# acceleration_particul_ariel.net
KiCad netlist of a schematic drawn in EasyEDA
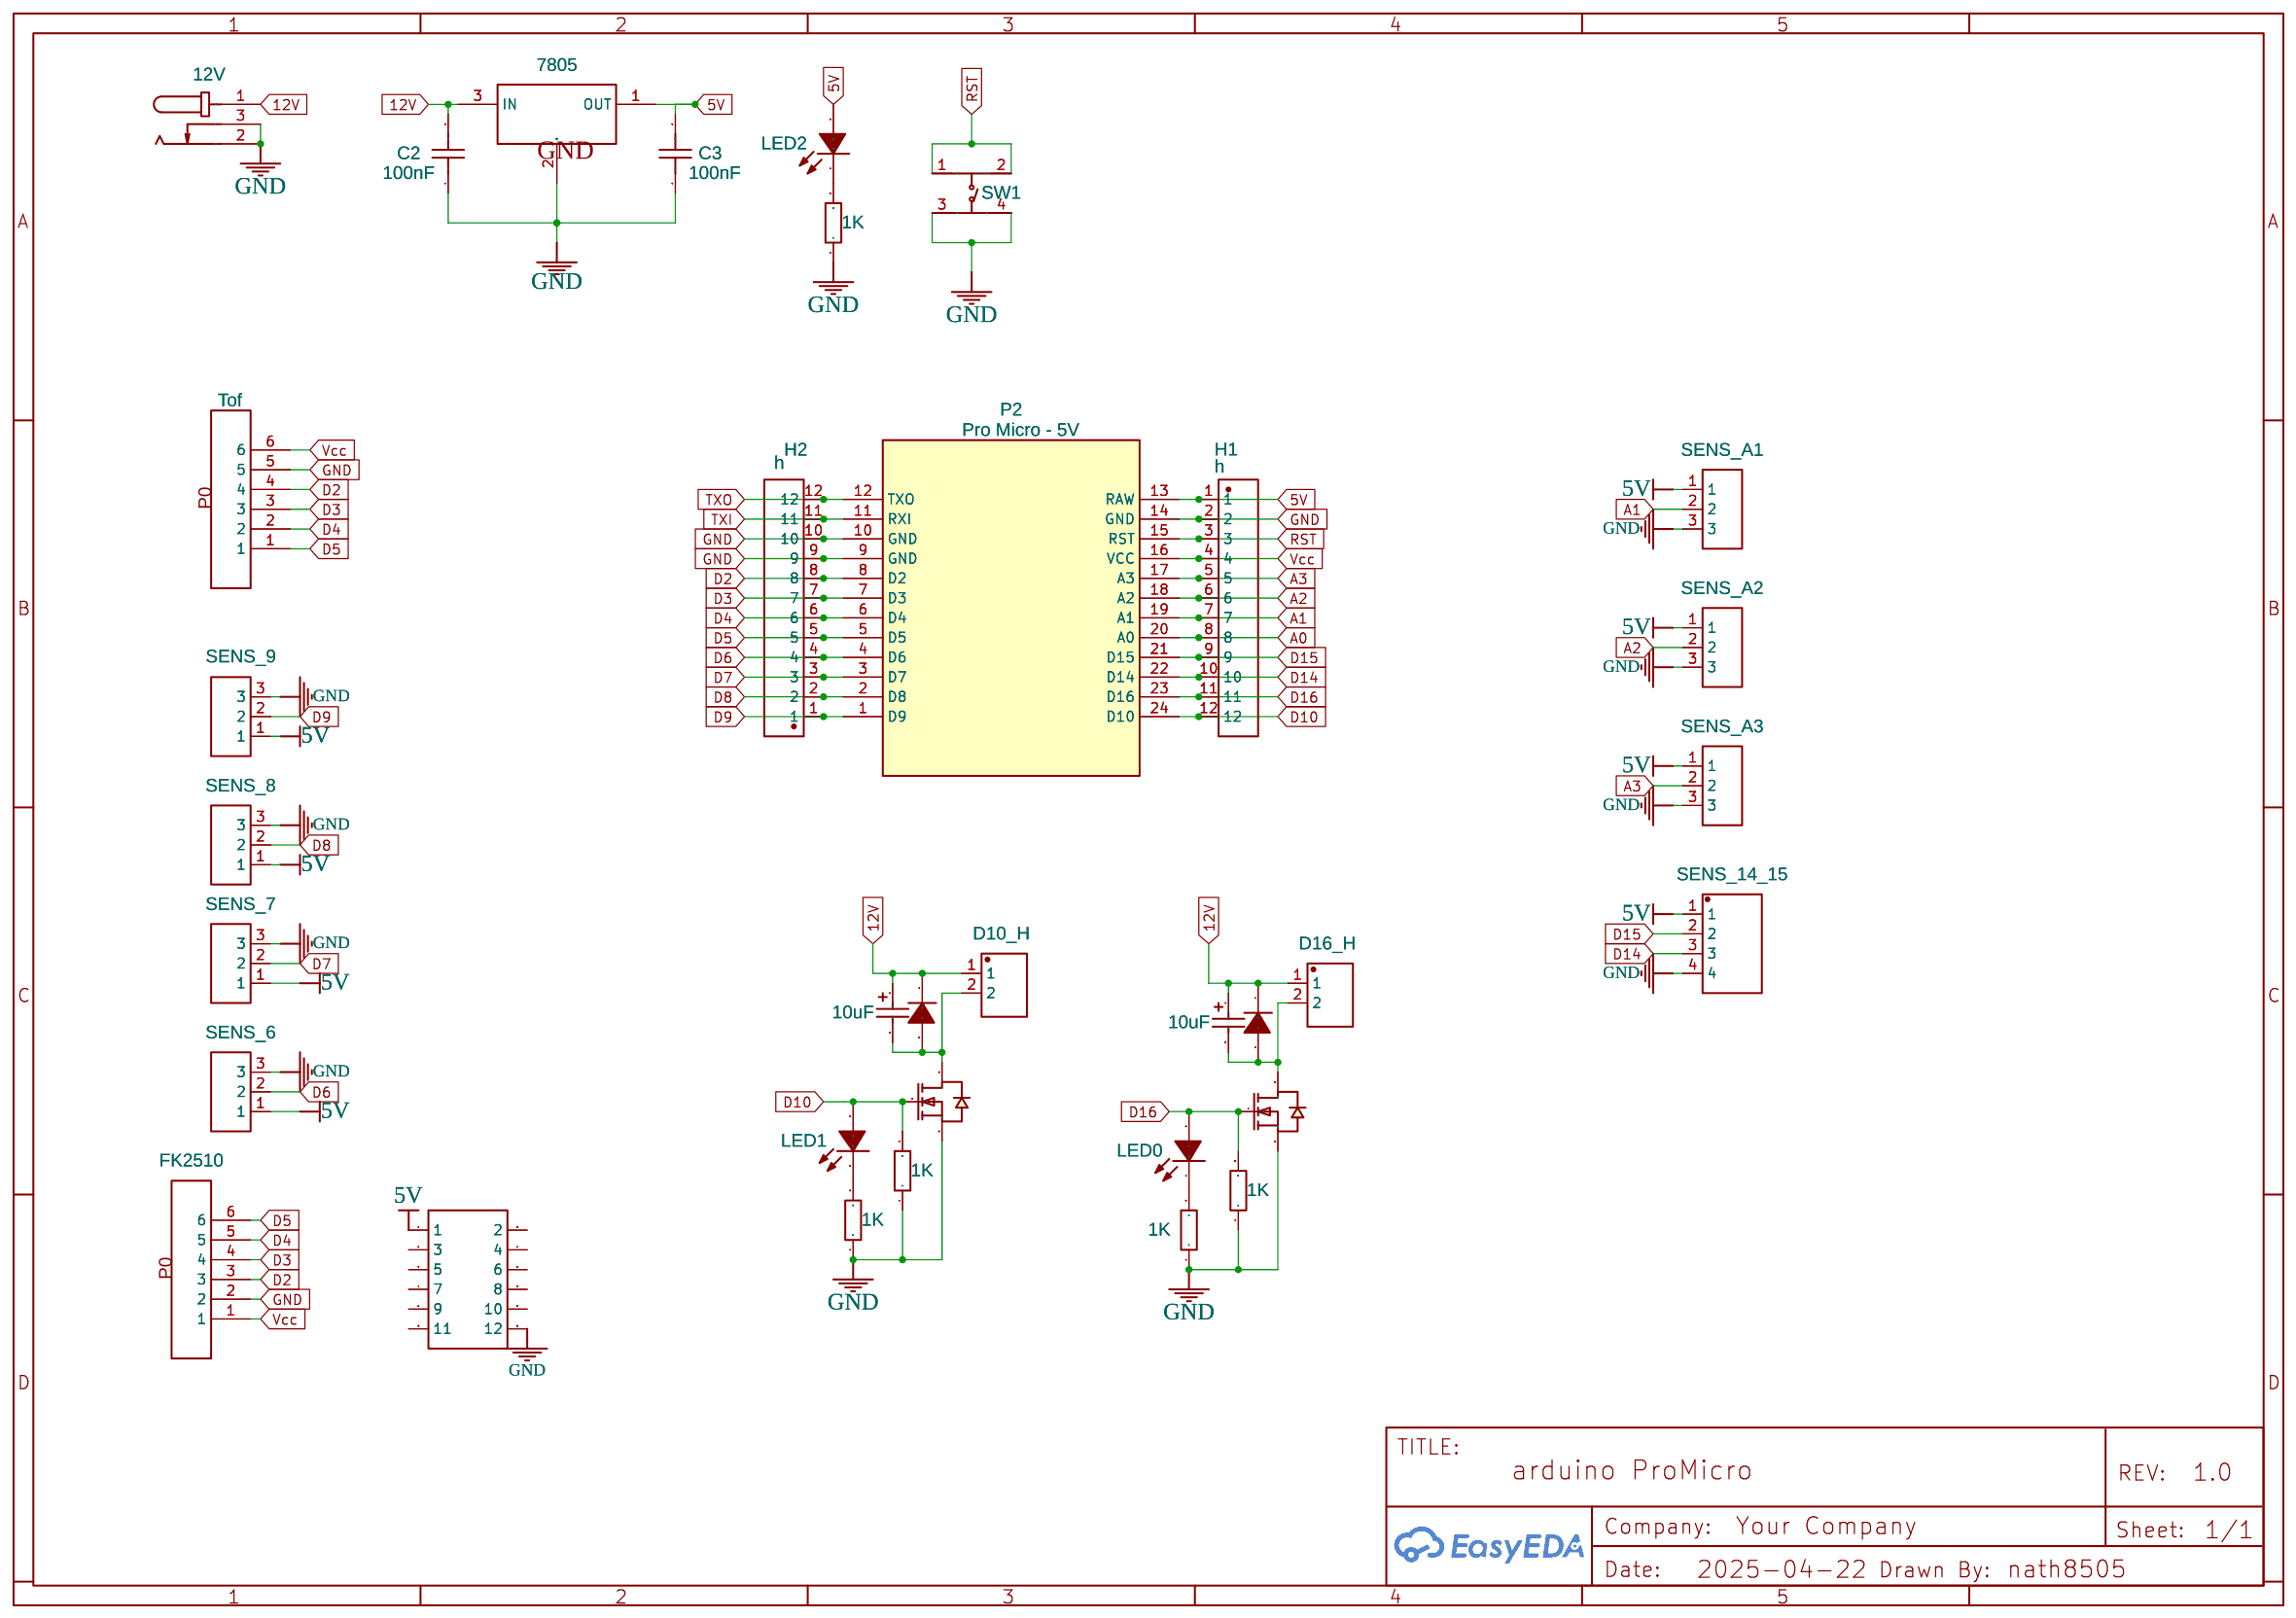
[diagram p0: schematic sheet]

(export (version "E")
  (design (tool "Eeschema 10.0.6"))
  (components
    (comp (ref "12V")
      (value "12V")
      (fields (field (name "Manufacturer Part") "DC005-2.0MM") (field (name "Manufacturer") "SOFNG"))
      (libsource (lib "") (part "DC005-2.0MM"))
    )
    (comp (ref "7805")
      (value "SE78L05")
      (fields (field (name "Manufacturer") "SEAWARD(思旺)"))
      (libsource (lib "") (part "SE78L05"))
    )
    (comp (ref "C0") (value "10uF") (libsource (lib "") (part "TAJA106K016RNJ")))
    (comp (ref "C1") (value "10uF") (libsource (lib "") (part "TAJA106K016RNJ")))
    (comp (ref "C2") (value "100nF") (libsource (lib "") (part "CC0603KRX7R9BB104")))
    (comp (ref "C3") (value "100nF") (libsource (lib "") (part "CC0603KRX7R9BB104")))
    (comp (ref "D0")
      (value "1N4007")
      (fields (field (name "Manufacturer Part") "1N4007F") (field (name "Manufacturer") "SK"))
      (libsource (lib "") (part "1N4007F"))
    )
    (comp (ref "D1")
      (value "1N4007")
      (fields (field (name "Manufacturer Part") "1N4007F") (field (name "Manufacturer") "SK"))
      (libsource (lib "") (part "1N4007F"))
    )
    (comp (ref "D10_H")
      (value "KF2510-2A")
      (fields (field (name "Manufacturer") "BOOMELE"))
      (libsource (lib "") (part "KF2510-2A"))
    )
    (comp (ref "D16_H")
      (value "KF2510-2A")
      (fields (field (name "Manufacturer") "BOOMELE"))
      (libsource (lib "") (part "KF2510-2A_1"))
    )
    (comp (ref "H1")
      (value "h")
      (fields (field (name "Manufacturer Part") "DS1021-1x12SF11-B") (field (name "Manufacturer") "CONNFLY"))
      (libsource (lib "") (part "DS1021-1X12SF11-B"))
    )
    (comp (ref "H2")
      (value "h")
      (fields (field (name "Manufacturer Part") "DS1021-1x12SF11-B") (field (name "Manufacturer") "CONNFLY"))
      (libsource (lib "") (part "DS1021-1X12SF11-B_1"))
    )
    (comp (ref "H4")
      (value "Header-Female-2.54_2x6")
      (fields (field (name "Manufacturer Part") "2.54-2*6P母") (field (name "Manufacturer") "BOOMELE(博穆精密)"))
      (libsource (lib "") (part "Header-Female-2.54_2x6"))
    )
    (comp (ref "I2C_TOF1") (value "Tof") (libsource (lib "") (part "PinHeader6")))
    (comp (ref "I2C_TOF2") (value "FK2510") (libsource (lib "") (part "PinHeader6")))
    (comp (ref "LED0")
      (value "KT-0603R")
      (fields (field (name "Manufacturer") "KENTO"))
      (libsource (lib "") (part "KT-0603R"))
    )
    (comp (ref "LED1")
      (value "KT-0603R")
      (fields (field (name "Manufacturer") "KENTO"))
      (libsource (lib "") (part "KT-0603R"))
    )
    (comp (ref "LED2")
      (value "KT-0603R")
      (fields (field (name "Manufacturer") "KENTO"))
      (libsource (lib "") (part "KT-0603R"))
    )
    (comp (ref "P2") (value "Pro Micro - 5V") (libsource (lib "") (part "Pro Micro - 5V")))
    (comp (ref "R0")
      (value "1K")
      (fields (field (name "Manufacturer Part") "0603WAF1001T5E") (field (name "Manufacturer") "UniOhm"))
      (libsource (lib "") (part "0603WAF1001T5E"))
    )
    (comp (ref "R1")
      (value "1K")
      (fields (field (name "Manufacturer Part") "0603WAF1001T5E") (field (name "Manufacturer") "UniOhm"))
      (libsource (lib "") (part "0603WAF1001T5E"))
    )
    (comp (ref "R2")
      (value "1K")
      (fields (field (name "Manufacturer Part") "0603WAF1001T5E") (field (name "Manufacturer") "UniOhm"))
      (libsource (lib "") (part "0603WAF1001T5E"))
    )
    (comp (ref "R3")
      (value "1K")
      (fields (field (name "Manufacturer Part") "0603WAF1001T5E") (field (name "Manufacturer") "UniOhm"))
      (libsource (lib "") (part "0603WAF1001T5E"))
    )
    (comp (ref "R4")
      (value "1K")
      (fields (field (name "Manufacturer Part") "0603WAF1001T5E") (field (name "Manufacturer") "UniOhm"))
      (libsource (lib "") (part "0603WAF1001T5E"))
    )
    (comp (ref "SENS_6") (value "FK2510") (libsource (lib "") (part "kf2510_3A")))
    (comp (ref "SENS_7") (value "FK2510") (libsource (lib "") (part "kf2510_3A")))
    (comp (ref "SENS_8") (value "FK2510") (libsource (lib "") (part "kf2510_3A")))
    (comp (ref "SENS_9") (value "FK2510") (libsource (lib "") (part "kf2510_3A")))
    (comp (ref "SENS_14_15")
      (value "SENS_14_15")
      (fields
        (field (name "Manufacturer Part") "210S-1*4P L=11.6MMGold-plated black")
        (field (name "Manufacturer") "Ckmtw")
      )
      (libsource (lib "") (part "Conector KF2510_3A.ventilador.4pin"))
    )
    (comp (ref "SENS_A1") (value "FK2510") (libsource (lib "") (part "kf2510_3A_1")))
    (comp (ref "SENS_A2") (value "FK2510") (libsource (lib "") (part "kf2510_3A_1")))
    (comp (ref "SENS_A3") (value "FK2510") (libsource (lib "") (part "kf2510_3A_1")))
    (comp (ref "SW1")
      (value "TC-6610-7-160G")
      (fields (field (name "Manufacturer") "HCTL(华灿天禄)"))
      (libsource (lib "") (part "TC-6610-7-160G"))
    )
    (comp (ref "T1")
      (value "Q")
      (fields (field (name "Manufacturer Part") "AO3400") (field (name "Manufacturer") "ElecSuper(静芯微）"))
      (libsource (lib "") (part "JSM2302"))
    )
    (comp (ref "T2")
      (value "Q")
      (fields (field (name "Manufacturer Part") "AO3400") (field (name "Manufacturer") "ElecSuper(静芯微）"))
      (libsource (lib "") (part "JSM2302"))
    )
  )
  (nets
    (net (code "1") (name "5V") (class "Default")
      (node (ref "7805") (pin "1") (pinfunction "OUT_1") (pintype "passive"))
      (node (ref "C3") (pin "2") (pinfunction "2_2") (pintype "unspecified"))
      (node (ref "H1") (pin "1") (pinfunction "1_1") (pintype "unspecified"))
      (node (ref "H4") (pin "1") (pinfunction "1_1") (pintype "input"))
      (node (ref "LED2") (pin "2") (pinfunction "A_2") (pintype "unspecified"))
      (node (ref "P2") (pin "13") (pinfunction "RAW_13") (pintype "unspecified"))
      (node (ref "SENS_14_15") (pin "1") (pinfunction "1_1") (pintype "unspecified"))
      (node (ref "SENS_6") (pin "1") (pinfunction "1_1") (pintype "unspecified"))
      (node (ref "SENS_7") (pin "1") (pinfunction "1_1") (pintype "unspecified"))
      (node (ref "SENS_8") (pin "1") (pinfunction "1_1") (pintype "unspecified"))
      (node (ref "SENS_9") (pin "1") (pinfunction "1_1") (pintype "unspecified"))
      (node (ref "SENS_A1") (pin "1") (pinfunction "1_1") (pintype "unspecified"))
      (node (ref "SENS_A2") (pin "1") (pinfunction "1_1") (pintype "unspecified"))
      (node (ref "SENS_A3") (pin "1") (pinfunction "1_1") (pintype "unspecified"))
    )
    (net (code "2") (name "12V") (class "Default")
      (node (ref "12V") (pin "1") (pinfunction "1_1") (pintype "unspecified"))
      (node (ref "7805") (pin "3") (pinfunction "IN_3") (pintype "passive"))
      (node (ref "C0") (pin "1") (pinfunction "1_1") (pintype "input"))
      (node (ref "C1") (pin "1") (pinfunction "1_1") (pintype "input"))
      (node (ref "C2") (pin "2") (pinfunction "2_2") (pintype "unspecified"))
      (node (ref "D0") (pin "1") (pinfunction "C_1") (pintype "unspecified"))
      (node (ref "D1") (pin "1") (pinfunction "C_1") (pintype "unspecified"))
      (node (ref "D10_H") (pin "1") (pinfunction "1_1") (pintype "unspecified"))
      (node (ref "D16_H") (pin "1") (pinfunction "1_1") (pintype "unspecified"))
    )
    (net (code "3") (name "A0") (class "Default")
      (node (ref "H1") (pin "8") (pinfunction "8_8") (pintype "unspecified"))
      (node (ref "P2") (pin "20") (pinfunction "A0_20") (pintype "unspecified"))
    )
    (net (code "4") (name "A1") (class "Default")
      (node (ref "H1") (pin "7") (pinfunction "7_7") (pintype "unspecified"))
      (node (ref "P2") (pin "19") (pinfunction "A1_19") (pintype "unspecified"))
      (node (ref "SENS_A1") (pin "2") (pinfunction "2_2") (pintype "unspecified"))
    )
    (net (code "5") (name "A2") (class "Default")
      (node (ref "H1") (pin "6") (pinfunction "6_6") (pintype "unspecified"))
      (node (ref "P2") (pin "18") (pinfunction "A2_18") (pintype "unspecified"))
      (node (ref "SENS_A2") (pin "2") (pinfunction "2_2") (pintype "unspecified"))
    )
    (net (code "6") (name "A3") (class "Default")
      (node (ref "H1") (pin "5") (pinfunction "5_5") (pintype "unspecified"))
      (node (ref "P2") (pin "17") (pinfunction "A3_17") (pintype "unspecified"))
      (node (ref "SENS_A3") (pin "2") (pinfunction "2_2") (pintype "unspecified"))
    )
    (net (code "7") (name "D2") (class "Default")
      (node (ref "H2") (pin "8") (pinfunction "8_8") (pintype "unspecified"))
      (node (ref "I2C_TOF1") (pin "4") (pinfunction "4_4") (pintype "unspecified"))
      (node (ref "I2C_TOF2") (pin "3") (pinfunction "3_3") (pintype "unspecified"))
      (node (ref "P2") (pin "8") (pinfunction "D2_8") (pintype "unspecified"))
    )
    (net (code "8") (name "D3") (class "Default")
      (node (ref "H2") (pin "7") (pinfunction "7_7") (pintype "unspecified"))
      (node (ref "I2C_TOF1") (pin "3") (pinfunction "3_3") (pintype "unspecified"))
      (node (ref "I2C_TOF2") (pin "4") (pinfunction "4_4") (pintype "unspecified"))
      (node (ref "P2") (pin "7") (pinfunction "D3_7") (pintype "unspecified"))
    )
    (net (code "9") (name "D4") (class "Default")
      (node (ref "H2") (pin "6") (pinfunction "6_6") (pintype "unspecified"))
      (node (ref "I2C_TOF1") (pin "2") (pinfunction "2_2") (pintype "unspecified"))
      (node (ref "I2C_TOF2") (pin "5") (pinfunction "5_5") (pintype "unspecified"))
      (node (ref "P2") (pin "6") (pinfunction "D4_6") (pintype "unspecified"))
    )
    (net (code "10") (name "D5") (class "Default")
      (node (ref "H2") (pin "5") (pinfunction "5_5") (pintype "unspecified"))
      (node (ref "I2C_TOF1") (pin "1") (pinfunction "1_1") (pintype "unspecified"))
      (node (ref "I2C_TOF2") (pin "6") (pinfunction "6_6") (pintype "unspecified"))
      (node (ref "P2") (pin "5") (pinfunction "D5_5") (pintype "unspecified"))
    )
    (net (code "11") (name "D6") (class "Default")
      (node (ref "H2") (pin "4") (pinfunction "4_4") (pintype "unspecified"))
      (node (ref "P2") (pin "4") (pinfunction "D6_4") (pintype "unspecified"))
      (node (ref "SENS_6") (pin "2") (pinfunction "2_2") (pintype "unspecified"))
    )
    (net (code "12") (name "D7") (class "Default")
      (node (ref "H2") (pin "3") (pinfunction "3_3") (pintype "unspecified"))
      (node (ref "P2") (pin "3") (pinfunction "D7_3") (pintype "unspecified"))
      (node (ref "SENS_7") (pin "2") (pinfunction "2_2") (pintype "unspecified"))
    )
    (net (code "13") (name "D8") (class "Default")
      (node (ref "H2") (pin "2") (pinfunction "2_2") (pintype "unspecified"))
      (node (ref "P2") (pin "2") (pinfunction "D8_2") (pintype "unspecified"))
      (node (ref "SENS_8") (pin "2") (pinfunction "2_2") (pintype "unspecified"))
    )
    (net (code "14") (name "D9") (class "Default")
      (node (ref "H2") (pin "1") (pinfunction "1_1") (pintype "unspecified"))
      (node (ref "P2") (pin "1") (pinfunction "D9_1") (pintype "unspecified"))
      (node (ref "SENS_9") (pin "2") (pinfunction "2_2") (pintype "unspecified"))
    )
    (net (code "15") (name "D10") (class "Default")
      (node (ref "H1") (pin "12") (pinfunction "12_12") (pintype "unspecified"))
      (node (ref "LED1") (pin "2") (pinfunction "A_2") (pintype "unspecified"))
      (node (ref "P2") (pin "24") (pinfunction "D10_24") (pintype "unspecified"))
      (node (ref "R2") (pin "2") (pinfunction "2_2") (pintype "input"))
      (node (ref "T1") (pin "1") (pinfunction "G_1") (pintype "unspecified"))
    )
    (net (code "16") (name "D14") (class "Default")
      (node (ref "H1") (pin "10") (pinfunction "10_10") (pintype "unspecified"))
      (node (ref "P2") (pin "22") (pinfunction "D14_22") (pintype "unspecified"))
      (node (ref "SENS_14_15") (pin "3") (pinfunction "3_3") (pintype "unspecified"))
    )
    (net (code "17") (name "D15") (class "Default")
      (node (ref "H1") (pin "9") (pinfunction "9_9") (pintype "unspecified"))
      (node (ref "P2") (pin "21") (pinfunction "D15_21") (pintype "unspecified"))
      (node (ref "SENS_14_15") (pin "2") (pinfunction "2_2") (pintype "unspecified"))
    )
    (net (code "18") (name "D16") (class "Default")
      (node (ref "H1") (pin "11") (pinfunction "11_11") (pintype "unspecified"))
      (node (ref "LED0") (pin "2") (pinfunction "A_2") (pintype "unspecified"))
      (node (ref "P2") (pin "23") (pinfunction "D16_23") (pintype "unspecified"))
      (node (ref "R1") (pin "2") (pinfunction "2_2") (pintype "input"))
      (node (ref "T2") (pin "1") (pinfunction "G_1") (pintype "unspecified"))
    )
    (net (code "19") (name "GND") (class "Default")
      (node (ref "12V") (pin "2") (pinfunction "2_2") (pintype "unspecified"))
      (node (ref "12V") (pin "3") (pinfunction "3_3") (pintype "unspecified"))
      (node (ref "7805") (pin "2") (pinfunction "GND_2") (pintype "unspecified"))
      (node (ref "C2") (pin "1") (pinfunction "1_1") (pintype "unspecified"))
      (node (ref "C3") (pin "1") (pinfunction "1_1") (pintype "unspecified"))
      (node (ref "H1") (pin "2") (pinfunction "2_2") (pintype "unspecified"))
      (node (ref "H2") (pin "10") (pinfunction "10_10") (pintype "unspecified"))
      (node (ref "H2") (pin "9") (pinfunction "9_9") (pintype "unspecified"))
      (node (ref "H4") (pin "12") (pinfunction "12_12") (pintype "input"))
      (node (ref "I2C_TOF1") (pin "5") (pinfunction "5_5") (pintype "unspecified"))
      (node (ref "I2C_TOF2") (pin "2") (pinfunction "2_2") (pintype "unspecified"))
      (node (ref "P2") (pin "10") (pinfunction "GND_10") (pintype "unspecified"))
      (node (ref "P2") (pin "14") (pinfunction "GND_14") (pintype "unspecified"))
      (node (ref "P2") (pin "9") (pinfunction "GND_9") (pintype "unspecified"))
      (node (ref "R0") (pin "1") (pinfunction "1_1") (pintype "input"))
      (node (ref "R1") (pin "1") (pinfunction "1_1") (pintype "input"))
      (node (ref "R2") (pin "1") (pinfunction "1_1") (pintype "input"))
      (node (ref "R3") (pin "1") (pinfunction "1_1") (pintype "input"))
      (node (ref "R4") (pin "1") (pinfunction "1_1") (pintype "input"))
      (node (ref "SENS_14_15") (pin "4") (pinfunction "4_4") (pintype "unspecified"))
      (node (ref "SENS_6") (pin "3") (pinfunction "3_3") (pintype "unspecified"))
      (node (ref "SENS_7") (pin "3") (pinfunction "3_3") (pintype "unspecified"))
      (node (ref "SENS_8") (pin "3") (pinfunction "3_3") (pintype "unspecified"))
      (node (ref "SENS_9") (pin "3") (pinfunction "3_3") (pintype "unspecified"))
      (node (ref "SENS_A1") (pin "3") (pinfunction "3_3") (pintype "unspecified"))
      (node (ref "SENS_A2") (pin "3") (pinfunction "3_3") (pintype "unspecified"))
      (node (ref "SENS_A3") (pin "3") (pinfunction "3_3") (pintype "unspecified"))
      (node (ref "SW1") (pin "3") (pinfunction "3_3") (pintype "unspecified"))
      (node (ref "SW1") (pin "4") (pinfunction "4_4") (pintype "unspecified"))
      (node (ref "T1") (pin "2") (pinfunction "S_2") (pintype "unspecified"))
      (node (ref "T2") (pin "2") (pinfunction "S_2") (pintype "unspecified"))
    )
    (net (code "20") (name "Net-(D0-A)") (class "Default")
      (node (ref "C0") (pin "2") (pinfunction "2_2") (pintype "input"))
      (node (ref "D0") (pin "2") (pinfunction "A_2") (pintype "unspecified"))
      (node (ref "D10_H") (pin "2") (pinfunction "2_2") (pintype "unspecified"))
      (node (ref "T1") (pin "3") (pinfunction "D_3") (pintype "unspecified"))
    )
    (net (code "21") (name "Net-(D1-A)") (class "Default")
      (node (ref "C1") (pin "2") (pinfunction "2_2") (pintype "input"))
      (node (ref "D1") (pin "2") (pinfunction "A_2") (pintype "unspecified"))
      (node (ref "D16_H") (pin "2") (pinfunction "2_2") (pintype "unspecified"))
      (node (ref "T2") (pin "3") (pinfunction "D_3") (pintype "unspecified"))
    )
    (net (code "22") (name "Net-(LED0-K)") (class "Default")
      (node (ref "LED0") (pin "1") (pinfunction "K_1") (pintype "unspecified"))
      (node (ref "R0") (pin "2") (pinfunction "2_2") (pintype "input"))
    )
    (net (code "23") (name "Net-(LED1-K)") (class "Default")
      (node (ref "LED1") (pin "1") (pinfunction "K_1") (pintype "unspecified"))
      (node (ref "R3") (pin "2") (pinfunction "2_2") (pintype "input"))
    )
    (net (code "24") (name "Net-(LED2-K)") (class "Default")
      (node (ref "LED2") (pin "1") (pinfunction "K_1") (pintype "unspecified"))
      (node (ref "R4") (pin "2") (pinfunction "2_2") (pintype "input"))
    )
    (net (code "25") (name "RST") (class "Default")
      (node (ref "H1") (pin "3") (pinfunction "3_3") (pintype "unspecified"))
      (node (ref "P2") (pin "15") (pinfunction "RST_15") (pintype "unspecified"))
      (node (ref "SW1") (pin "1") (pinfunction "1_1") (pintype "unspecified"))
      (node (ref "SW1") (pin "2") (pinfunction "2_2") (pintype "unspecified"))
    )
    (net (code "26") (name "TXI") (class "Default")
      (node (ref "H2") (pin "11") (pinfunction "11_11") (pintype "unspecified"))
      (node (ref "P2") (pin "11") (pinfunction "RXI_11") (pintype "unspecified"))
    )
    (net (code "27") (name "TXO") (class "Default")
      (node (ref "H2") (pin "12") (pinfunction "12_12") (pintype "unspecified"))
      (node (ref "P2") (pin "12") (pinfunction "TXO_12") (pintype "unspecified"))
    )
    (net (code "28") (name "Vcc") (class "Default")
      (node (ref "H1") (pin "4") (pinfunction "4_4") (pintype "unspecified"))
      (node (ref "I2C_TOF1") (pin "6") (pinfunction "6_6") (pintype "unspecified"))
      (node (ref "I2C_TOF2") (pin "1") (pinfunction "1_1") (pintype "unspecified"))
      (node (ref "P2") (pin "16") (pinfunction "VCC_16") (pintype "unspecified"))
    )
    (net (code "29") (name "unconnected-(H4-Pad2)") (class "Default")
      (node (ref "H4") (pin "2") (pinfunction "2_2") (pintype "input"))
    )
    (net (code "30") (name "unconnected-(H4-Pad3)") (class "Default")
      (node (ref "H4") (pin "3") (pinfunction "3_3") (pintype "input"))
    )
    (net (code "31") (name "unconnected-(H4-Pad4)") (class "Default")
      (node (ref "H4") (pin "4") (pinfunction "4_4") (pintype "input"))
    )
    (net (code "32") (name "unconnected-(H4-Pad5)") (class "Default")
      (node (ref "H4") (pin "5") (pinfunction "5_5") (pintype "input"))
    )
    (net (code "33") (name "unconnected-(H4-Pad6)") (class "Default")
      (node (ref "H4") (pin "6") (pinfunction "6_6") (pintype "input"))
    )
    (net (code "34") (name "unconnected-(H4-Pad7)") (class "Default")
      (node (ref "H4") (pin "7") (pinfunction "7_7") (pintype "input"))
    )
    (net (code "35") (name "unconnected-(H4-Pad8)") (class "Default")
      (node (ref "H4") (pin "8") (pinfunction "8_8") (pintype "input"))
    )
    (net (code "36") (name "unconnected-(H4-Pad9)") (class "Default")
      (node (ref "H4") (pin "9") (pinfunction "9_9") (pintype "input"))
    )
    (net (code "37") (name "unconnected-(H4-Pad10)") (class "Default")
      (node (ref "H4") (pin "10") (pinfunction "10_10") (pintype "input"))
    )
    (net (code "38") (name "unconnected-(H4-Pad11)") (class "Default")
      (node (ref "H4") (pin "11") (pinfunction "11_11") (pintype "input"))
    )
  )
)
